# 12_Raspbbery_CM3.net
KiCad netlist of a schematic drawn in Altium Designer
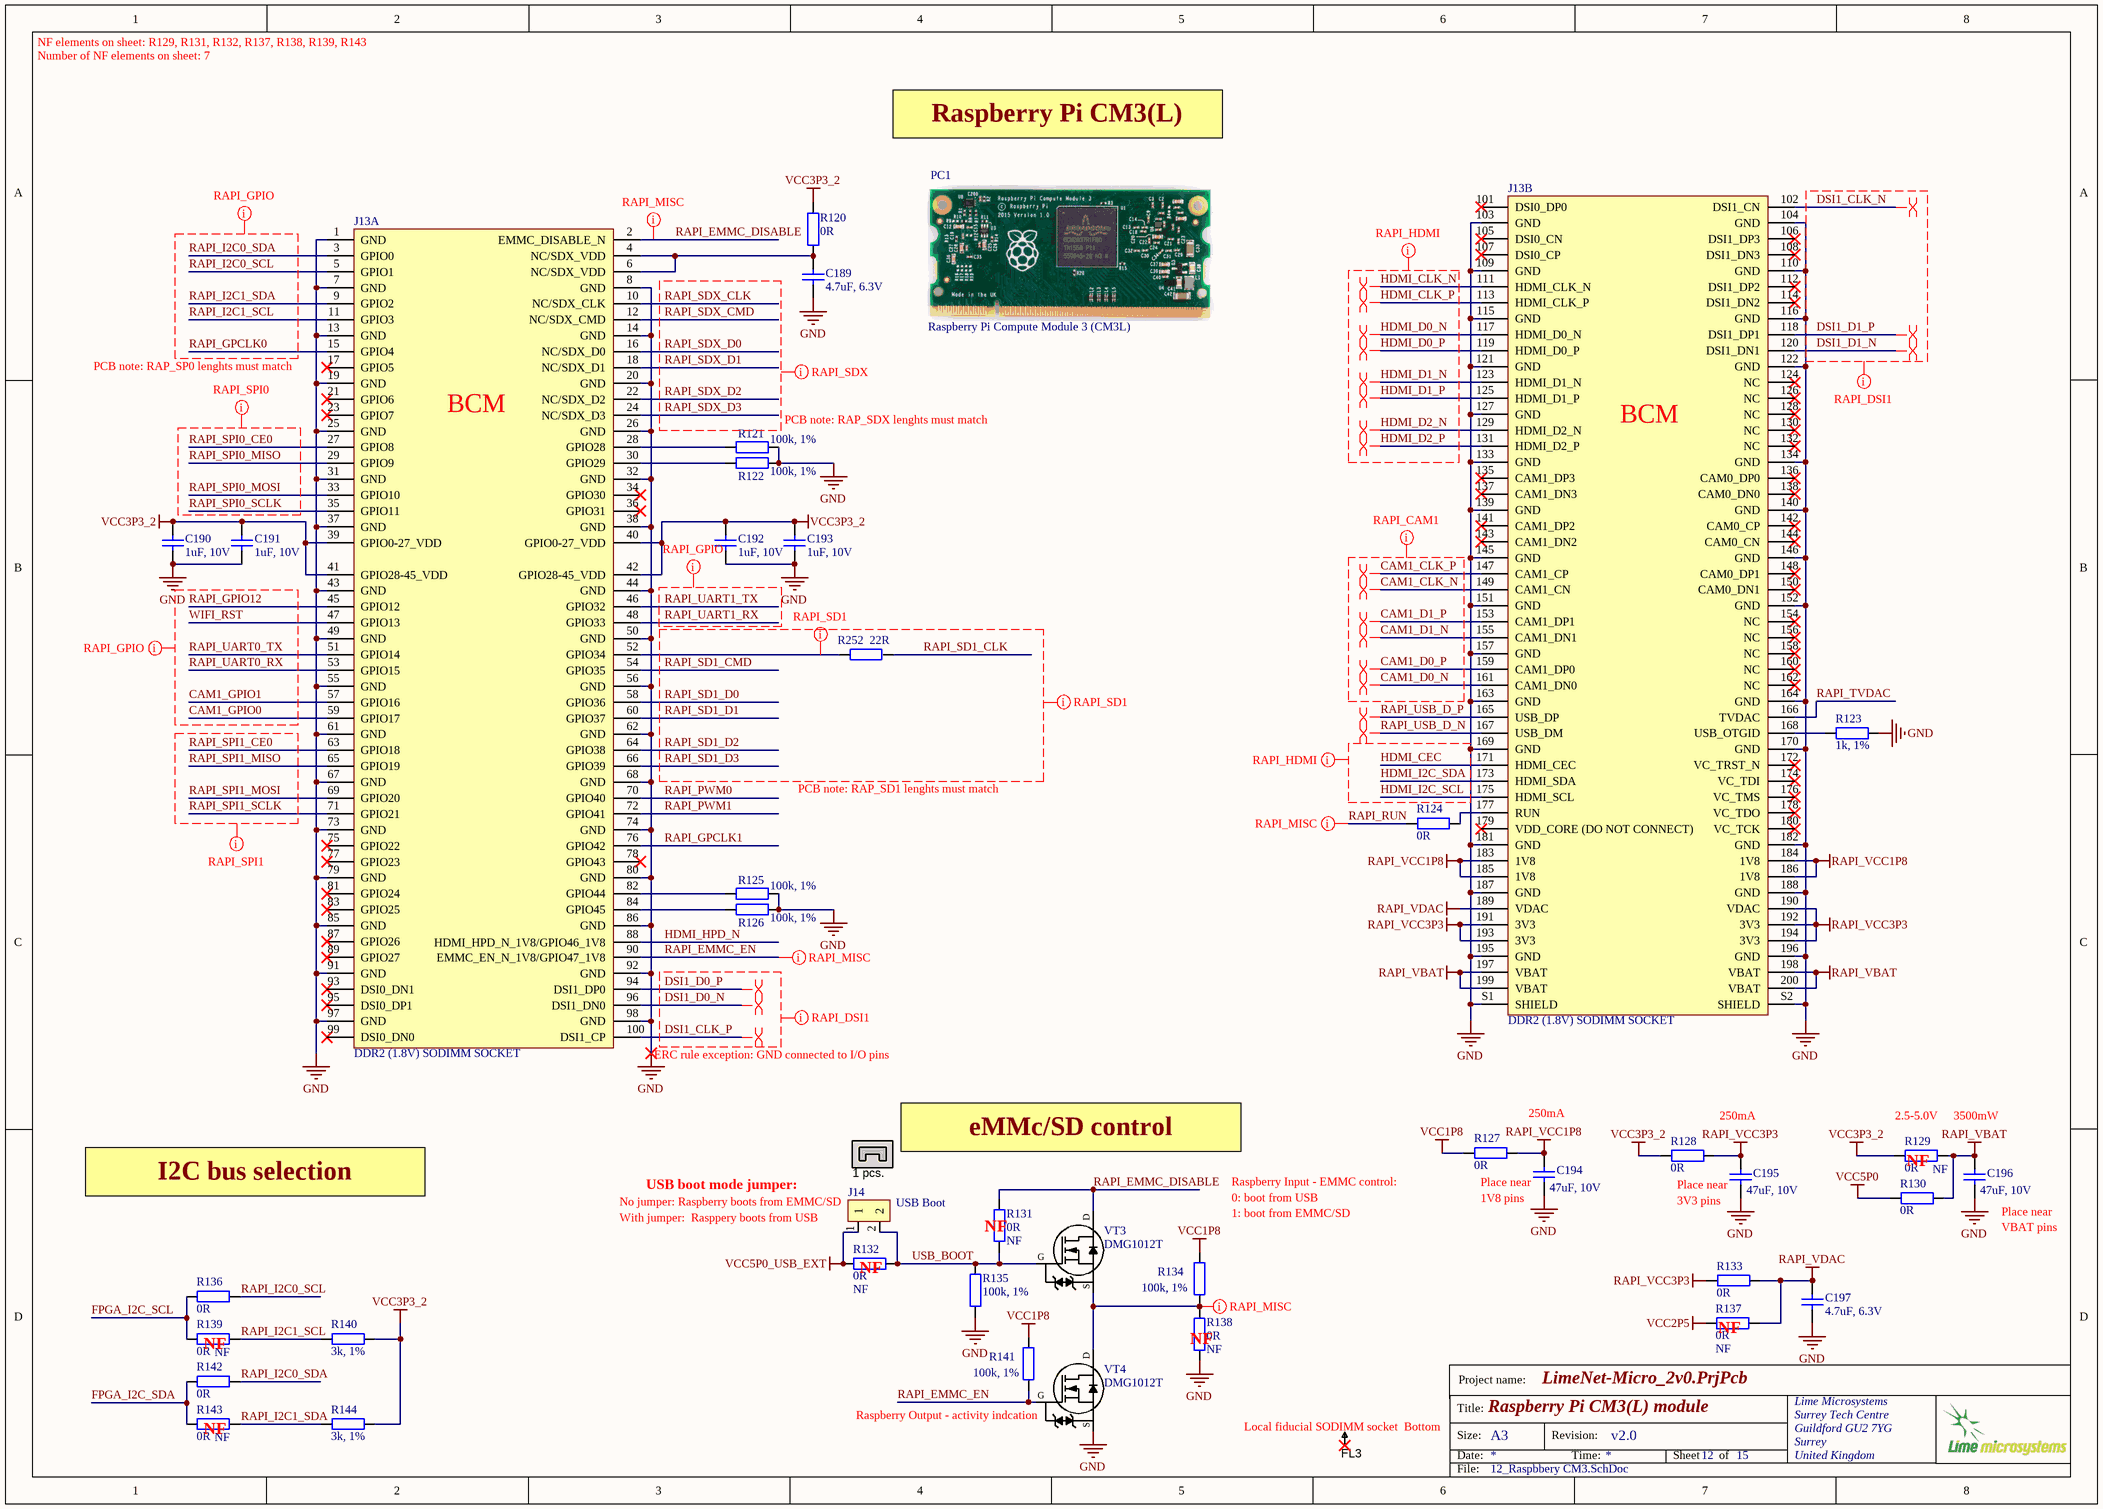
[diagram p0: 12_Raspbbery CM3.SchDoc]

(export (version "E")
  (design (tool "Eeschema 10.0.6"))
  (components
    (comp (ref "C189")
      (value "4.7uF, 6.3V")
      (footprint "CAP0402")
      (fields
        (field (name "MANUFACTURER") "Murata Electronics North America")
        (field (name "TOLERANCE") "±20%")
        (field (name "MANUFACTURER PART NUMBER") "GRM155R60J475ME87D")
      )
      (libsource (lib "LimeMicroAltiumLib_schLib") (part "Cap_0402"))
    )
    (comp (ref "C190")
      (value "1uF, 10V")
      (footprint "CAP0402")
      (description "CAP CER 1UF 10V X5R 0402")
      (fields
        (field (name "MANUFACTURER") "Yageo")
        (field (name "MANUFACTURER PART NUMBER") "CC0402MRX5R6BB105")
      )
      (libsource (lib "LimeMicroAltiumLib_schLib") (part "Cap_0402"))
    )
    (comp (ref "C191")
      (value "1uF, 10V")
      (footprint "CAP0402")
      (description "CAP CER 1UF 10V X5R 0402")
      (fields
        (field (name "MANUFACTURER") "Yageo")
        (field (name "MANUFACTURER PART NUMBER") "CC0402MRX5R6BB105")
      )
      (libsource (lib "LimeMicroAltiumLib_schLib") (part "Cap_0402"))
    )
    (comp (ref "C192")
      (value "1uF, 10V")
      (footprint "CAP0402")
      (description "CAP CER 1UF 10V X5R 0402")
      (fields
        (field (name "MANUFACTURER") "Yageo")
        (field (name "MANUFACTURER PART NUMBER") "CC0402MRX5R6BB105")
      )
      (libsource (lib "LimeMicroAltiumLib_schLib") (part "Cap_0402"))
    )
    (comp (ref "C193")
      (value "1uF, 10V")
      (footprint "CAP0402")
      (description "CAP CER 1UF 10V X5R 0402")
      (fields
        (field (name "MANUFACTURER") "Yageo")
        (field (name "MANUFACTURER PART NUMBER") "CC0402MRX5R6BB105")
      )
      (libsource (lib "LimeMicroAltiumLib_schLib") (part "Cap_0402"))
    )
    (comp (ref "C194")
      (value "47uF, 10V")
      (footprint "CAP1206")
      (fields (field (name "TOLERANCE") "±20%") (field (name "MANUFACTURER") "TDK Corporation"))
      (libsource (lib "LimeFPGAboard_schLib") (part "Cap_1206"))
    )
    (comp (ref "C195")
      (value "47uF, 10V")
      (footprint "CAP1206")
      (fields (field (name "TOLERANCE") "±20%") (field (name "MANUFACTURER") "TDK Corporation"))
      (libsource (lib "LimeFPGAboard_schLib") (part "Cap_1206"))
    )
    (comp (ref "C196")
      (value "47uF, 10V")
      (footprint "CAP1206")
      (fields (field (name "TOLERANCE") "±20%") (field (name "MANUFACTURER") "TDK Corporation"))
      (libsource (lib "LimeFPGAboard_schLib") (part "Cap_1206"))
    )
    (comp (ref "C197")
      (value "4.7uF, 6.3V")
      (footprint "CAP0402")
      (fields
        (field (name "MANUFACTURER") "Murata Electronics North America")
        (field (name "TOLERANCE") "±20%")
        (field (name "MANUFACTURER PART NUMBER") "GRM155R60J475ME87D")
      )
      (libsource (lib "LimeMicroAltiumLib_schLib") (part "Cap_0402"))
    )
    (comp (ref "FL3")
      (value "Fiducial")
      (footprint "Fiducial_local")
      (libsource (lib "VGTU_Altium_lib") (part "Fiducial"))
    )
    (comp (ref "J13")
      (value "DDR2 (1.8V) SODIMM SOCKET")
      (footprint "TE_1717254-1_DDR_SODIMM")
      (fields
        (field (name "MANUFACTURER") "TE Connectivity AMP Connectors")
        (field (name "MANUFACTURER PART NUMBER") "1717254-4")
      )
      (libsource (lib "LimeMicroAltiumLib_schLib_r01") (part "1717254-1"))
    )
    (comp (ref "J14")
      (value "USB Boot")
      (footprint "HDR_1x2")
      (fields (field (name "MANUFACTURER") "3M"))
      (libsource (lib "LimeFPGAboard_schLib") (part "Jumper"))
    )
    (comp (ref "JMP1")
      (value "1 pcs.")
      (description "Shorting Jumper, 2-position, 1.27mm pitch")
      (fields (field (name "MANUFACTURER") "Sullins"))
      (libsource (lib "LimeMicroAltiumLib_schLib") (part "JUMP_2P_CONN_HEADER"))
    )
    (comp (ref "PC1")
      (value "Raspberry Pi Compute Module 3 (CM3L)")
      (fields (field (name "MANUFACTURER") "RASPBERRY-PI"))
      (libsource (lib "LimeMicroAltiumLib_schLib_r01") (part "Raspberry_RPI-COMPUTE3"))
    )
    (comp (ref "R120")
      (value "0R")
      (footprint "RES0402")
      (fields (field (name "MANUFACTURER") "Yageo"))
      (libsource (lib "LimeFPGAboard_schLib") (part "Res_0402"))
    )
    (comp (ref "R121")
      (value "100k, 1%")
      (footprint "RES0402")
      (fields
        (field (name "MANUFACTURER") "Vishay Dale")
        (field (name "TOLERANCE") "±1%")
        (field (name "MANUFACTURER PART NUMBER") "CRCW0402100KFKEDC")
      )
      (libsource (lib "LimeMicroAltiumLib_schLib") (part "Res_0402"))
    )
    (comp (ref "R122")
      (value "100k, 1%")
      (footprint "RES0402")
      (fields
        (field (name "MANUFACTURER") "Vishay Dale")
        (field (name "TOLERANCE") "±1%")
        (field (name "MANUFACTURER PART NUMBER") "CRCW0402100KFKEDC")
      )
      (libsource (lib "LimeMicroAltiumLib_schLib") (part "Res_0402"))
    )
    (comp (ref "R123")
      (value "1k, 1%")
      (footprint "RES0402")
      (fields (field (name "MANUFACTURER") "Stackpole Electronics Inc") (field (name "TOLERANCE") "±1%"))
      (libsource (lib "LimeMicroAltiumLib_schLib") (part "Res_0402"))
    )
    (comp (ref "R124")
      (value "0R")
      (footprint "RES0402")
      (fields (field (name "MANUFACTURER") "Yageo"))
      (libsource (lib "LimeFPGAboard_schLib") (part "Res_0402"))
    )
    (comp (ref "R125")
      (value "100k, 1%")
      (footprint "RES0402")
      (fields
        (field (name "MANUFACTURER") "Vishay Dale")
        (field (name "TOLERANCE") "±1%")
        (field (name "MANUFACTURER PART NUMBER") "CRCW0402100KFKEDC")
      )
      (libsource (lib "LimeMicroAltiumLib_schLib") (part "Res_0402"))
    )
    (comp (ref "R126")
      (value "100k, 1%")
      (footprint "RES0402")
      (fields
        (field (name "MANUFACTURER") "Vishay Dale")
        (field (name "TOLERANCE") "±1%")
        (field (name "MANUFACTURER PART NUMBER") "CRCW0402100KFKEDC")
      )
      (libsource (lib "LimeMicroAltiumLib_schLib") (part "Res_0402"))
    )
    (comp (ref "R127")
      (value "0R")
      (footprint "RES0805")
      (fields (field (name "MANUFACTURER") "Vishay Dale") (field (name "TOLERANCE") "Jumper"))
      (libsource (lib "LimeMicroAltiumLib_schLib") (part "Res_0402"))
    )
    (comp (ref "R128")
      (value "0R")
      (footprint "RES0805")
      (fields (field (name "MANUFACTURER") "Vishay Dale") (field (name "TOLERANCE") "Jumper"))
      (libsource (lib "LimeMicroAltiumLib_schLib") (part "Res_0402"))
    )
    (comp (ref "R129")
      (value "0R")
      (footprint "RES0805")
      (fields
        (field (name "ASSEMBLY INFO") "NF")
        (field (name "MANUFACTURER") "Vishay Dale")
        (field (name "TOLERANCE") "Jumper")
      )
      (libsource (lib "LimeMicroAltiumLib_schLib") (part "Res_0402"))
    )
    (comp (ref "R130")
      (value "0R")
      (footprint "RES0805")
      (fields (field (name "MANUFACTURER") "Vishay Dale") (field (name "TOLERANCE") "Jumper"))
      (libsource (lib "LimeMicroAltiumLib_schLib") (part "Res_0402"))
    )
    (comp (ref "R131")
      (value "0R")
      (footprint "RES0402")
      (fields (field (name "MANUFACTURER") "Yageo") (field (name "ASSEMBLY INFO") "NF"))
      (libsource (lib "LimeFPGAboard_schLib") (part "Res_0402"))
    )
    (comp (ref "R132")
      (value "0R")
      (footprint "RES0402")
      (fields
        (field (name "ASSEMBLY INFO") "NF")
        (field (name "MANUFACTURER") "Yageo")
        (field (name "TOLERANCE") "Jumper")
      )
      (libsource (lib "LimeMicroAltiumLib_schLib") (part "Res_0402"))
    )
    (comp (ref "R133")
      (value "0R")
      (footprint "RES0402")
      (fields (field (name "MANUFACTURER") "Yageo"))
      (libsource (lib "LimeFPGAboard_schLib") (part "Res_0402"))
    )
    (comp (ref "R134")
      (value "100k, 1%")
      (footprint "RES0402")
      (fields
        (field (name "MANUFACTURER") "Vishay Dale")
        (field (name "TOLERANCE") "±1%")
        (field (name "MANUFACTURER PART NUMBER") "CRCW0402100KFKEDC")
      )
      (libsource (lib "LimeMicroAltiumLib_schLib") (part "Res_0402"))
    )
    (comp (ref "R135")
      (value "100k, 1%")
      (footprint "RES0402")
      (fields
        (field (name "MANUFACTURER") "Vishay Dale")
        (field (name "TOLERANCE") "±1%")
        (field (name "MANUFACTURER PART NUMBER") "CRCW0402100KFKEDC")
      )
      (libsource (lib "LimeMicroAltiumLib_schLib") (part "Res_0402"))
    )
    (comp (ref "R136")
      (value "0R")
      (footprint "RES0402")
      (fields (field (name "MANUFACTURER") "Yageo"))
      (libsource (lib "LimeFPGAboard_schLib") (part "Res_0402"))
    )
    (comp (ref "R137")
      (value "0R")
      (footprint "RES0402")
      (fields (field (name "MANUFACTURER") "Yageo") (field (name "ASSEMBLY INFO") "NF"))
      (libsource (lib "LimeFPGAboard_schLib") (part "Res_0402"))
    )
    (comp (ref "R138")
      (value "0R")
      (footprint "RES0402")
      (fields (field (name "MANUFACTURER") "Yageo") (field (name "ASSEMBLY INFO") "NF"))
      (libsource (lib "LimeFPGAboard_schLib") (part "Res_0402"))
    )
    (comp (ref "R139")
      (value "0R")
      (footprint "RES0402")
      (fields (field (name "MANUFACTURER") "Yageo") (field (name "ASSEMBLY INFO") "NF"))
      (libsource (lib "LimeFPGAboard_schLib") (part "Res_0402"))
    )
    (comp (ref "R140")
      (value "3k, 1%")
      (footprint "RES0402")
      (fields (field (name "TOLERANCE") "±1%") (field (name "MANUFACTURER") "Vishay Dale"))
      (libsource (lib "LimeMicroAltiumLib_schLib") (part "Res_0402"))
    )
    (comp (ref "R141")
      (value "100k, 1%")
      (footprint "RES0402")
      (fields
        (field (name "MANUFACTURER") "Vishay Dale")
        (field (name "TOLERANCE") "±1%")
        (field (name "MANUFACTURER PART NUMBER") "CRCW0402100KFKEDC")
      )
      (libsource (lib "LimeMicroAltiumLib_schLib") (part "Res_0402"))
    )
    (comp (ref "R142")
      (value "0R")
      (footprint "RES0402")
      (fields (field (name "MANUFACTURER") "Yageo"))
      (libsource (lib "LimeFPGAboard_schLib") (part "Res_0402"))
    )
    (comp (ref "R143")
      (value "0R")
      (footprint "RES0402")
      (fields (field (name "MANUFACTURER") "Yageo") (field (name "ASSEMBLY INFO") "NF"))
      (libsource (lib "LimeFPGAboard_schLib") (part "Res_0402"))
    )
    (comp (ref "R144")
      (value "3k, 1%")
      (footprint "RES0402")
      (fields (field (name "TOLERANCE") "±1%") (field (name "MANUFACTURER") "Vishay Dale"))
      (libsource (lib "LimeMicroAltiumLib_schLib") (part "Res_0402"))
    )
    (comp (ref "R252")
      (value "22R")
      (footprint "RES0402")
      (fields (field (name "TOLERANCE") "±1%") (field (name "MANUFACTURER") "Yageo"))
      (libsource (lib "LimeFPGAboard_schLib") (part "Res_0402"))
    )
    (comp (ref "VT3")
      (value "DMG1012T")
      (footprint "SOT523")
      (fields
        (field (name "MANUFACTURER") "Diodes Incorporated")
        (field (name "MANUFACTURER PART NUMBER") "DMG1012TQ-7")
      )
      (libsource (lib "LimeMicroAltiumLib_schLib_r01") (part "DMG1012T"))
    )
    (comp (ref "VT4")
      (value "DMG1012T")
      (footprint "SOT523")
      (fields
        (field (name "MANUFACTURER") "Diodes Incorporated")
        (field (name "MANUFACTURER PART NUMBER") "DMG1012TQ-7")
      )
      (libsource (lib "LimeMicroAltiumLib_schLib_r01") (part "DMG1012T"))
    )
  )
  (nets
    (net (code "1") (name "/CAM1_CLK_N") (class "Default")
      (node (ref "J13") (pin "149") (pinfunction "CAM1_CN_149") (pintype "passive"))
    )
    (net (code "2") (name "/CAM1_CLK_P") (class "Default")
      (node (ref "J13") (pin "147") (pinfunction "CAM1_CP_147") (pintype "passive"))
    )
    (net (code "3") (name "/CAM1_D0_N") (class "Default")
      (node (ref "J13") (pin "161") (pinfunction "CAM1_DN0_161") (pintype "passive"))
    )
    (net (code "4") (name "/CAM1_D0_P") (class "Default")
      (node (ref "J13") (pin "159") (pinfunction "CAM1_DP0_159") (pintype "passive"))
    )
    (net (code "5") (name "/CAM1_D1_N") (class "Default")
      (node (ref "J13") (pin "155") (pinfunction "CAM1_DN1_155") (pintype "passive"))
    )
    (net (code "6") (name "/CAM1_D1_P") (class "Default")
      (node (ref "J13") (pin "153") (pinfunction "CAM1_DP1_153") (pintype "passive"))
    )
    (net (code "7") (name "/CAM1_GPIO0") (class "Default")
      (node (ref "J13") (pin "59") (pinfunction "GPIO17_59") (pintype "passive"))
    )
    (net (code "8") (name "/CAM1_GPIO1") (class "Default")
      (node (ref "J13") (pin "57") (pinfunction "GPIO16_57") (pintype "passive"))
    )
    (net (code "9") (name "/DSI1_CLK_N") (class "Default")
      (node (ref "J13") (pin "102") (pinfunction "DSI1_CN_102") (pintype "passive"))
    )
    (net (code "10") (name "/DSI1_CLK_P") (class "Default")
      (node (ref "J13") (pin "100") (pinfunction "DSI1_CP_100") (pintype "passive"))
    )
    (net (code "11") (name "/DSI1_D0_N") (class "Default")
      (node (ref "J13") (pin "96") (pinfunction "DSI1_DN0_96") (pintype "passive"))
    )
    (net (code "12") (name "/DSI1_D0_P") (class "Default")
      (node (ref "J13") (pin "94") (pinfunction "DSI1_DP0_94") (pintype "passive"))
    )
    (net (code "13") (name "/DSI1_D1_N") (class "Default")
      (node (ref "J13") (pin "120") (pinfunction "DSI1_DN1_120") (pintype "passive"))
    )
    (net (code "14") (name "/DSI1_D1_P") (class "Default")
      (node (ref "J13") (pin "118") (pinfunction "DSI1_DP1_118") (pintype "passive"))
    )
    (net (code "15") (name "/FPGA_I2C_SCL") (class "Default")
      (node (ref "R136") (pin "1") (pinfunction "1_1") (pintype "passive"))
      (node (ref "R139") (pin "1") (pinfunction "1_1") (pintype "passive"))
    )
    (net (code "16") (name "/FPGA_I2C_SDA") (class "Default")
      (node (ref "R142") (pin "1") (pinfunction "1_1") (pintype "passive"))
      (node (ref "R143") (pin "1") (pinfunction "1_1") (pintype "passive"))
    )
    (net (code "17") (name "/HDMI_CEC") (class "Default")
      (node (ref "J13") (pin "171") (pinfunction "HDMI_CEC_171") (pintype "passive"))
    )
    (net (code "18") (name "/HDMI_CLK_N") (class "Default")
      (node (ref "J13") (pin "111") (pinfunction "HDMI_CLK_N_111") (pintype "passive"))
    )
    (net (code "19") (name "/HDMI_CLK_P") (class "Default")
      (node (ref "J13") (pin "113") (pinfunction "HDMI_CLK_P_113") (pintype "passive"))
    )
    (net (code "20") (name "/HDMI_D0_N") (class "Default")
      (node (ref "J13") (pin "117") (pinfunction "HDMI_D0_N_117") (pintype "passive"))
    )
    (net (code "21") (name "/HDMI_D0_P") (class "Default")
      (node (ref "J13") (pin "119") (pinfunction "HDMI_D0_P_119") (pintype "passive"))
    )
    (net (code "22") (name "/HDMI_D1_N") (class "Default")
      (node (ref "J13") (pin "123") (pinfunction "HDMI_D1_N_123") (pintype "passive"))
    )
    (net (code "23") (name "/HDMI_D1_P") (class "Default")
      (node (ref "J13") (pin "125") (pinfunction "HDMI_D1_P_125") (pintype "passive"))
    )
    (net (code "24") (name "/HDMI_D2_N") (class "Default")
      (node (ref "J13") (pin "129") (pinfunction "HDMI_D2_N_129") (pintype "passive"))
    )
    (net (code "25") (name "/HDMI_D2_P") (class "Default")
      (node (ref "J13") (pin "131") (pinfunction "HDMI_D2_P_131") (pintype "passive"))
    )
    (net (code "26") (name "/HDMI_HPD_N") (class "Default")
      (node (ref "J13") (pin "88") (pinfunction "HDMI_HPD_N_1V8/GPIO46_1V8_88") (pintype "passive"))
    )
    (net (code "27") (name "/HDMI_I2C_SCL") (class "Default")
      (node (ref "J13") (pin "175") (pinfunction "HDMI_SCL_175") (pintype "passive"))
    )
    (net (code "28") (name "/HDMI_I2C_SDA") (class "Default")
      (node (ref "J13") (pin "173") (pinfunction "HDMI_SDA_173") (pintype "passive"))
    )
    (net (code "29") (name "/RAPI_EMMC_DISABLE") (class "Default")
      (node (ref "J13") (pin "2") (pinfunction "EMMC_DISABLE_N_2") (pintype "passive"))
      (node (ref "R131") (pin "1") (pinfunction "1_1") (pintype "passive"))
      (node (ref "VT3") (pin "D") (pinfunction "D_D") (pintype "passive"))
    )
    (net (code "30") (name "/RAPI_EMMC_EN") (class "Default")
      (node (ref "J13") (pin "90") (pinfunction "EMMC_EN_N_1V8/GPIO47_1V8_90") (pintype "passive"))
      (node (ref "R141") (pin "2") (pinfunction "2_2") (pintype "passive"))
      (node (ref "VT4") (pin "G") (pinfunction "G_G") (pintype "passive"))
    )
    (net (code "31") (name "/RAPI_GPCLK0") (class "Default")
      (node (ref "J13") (pin "15") (pinfunction "GPIO4_15") (pintype "passive"))
    )
    (net (code "32") (name "/RAPI_GPCLK1") (class "Default")
      (node (ref "J13") (pin "76") (pinfunction "GPIO42_76") (pintype "passive"))
    )
    (net (code "33") (name "/RAPI_GPIO12") (class "Default")
      (node (ref "J13") (pin "45") (pinfunction "GPIO12_45") (pintype "passive"))
    )
    (net (code "34") (name "/RAPI_I2C0_SCL") (class "Default")
      (node (ref "J13") (pin "5") (pinfunction "GPIO1_5") (pintype "passive"))
      (node (ref "R136") (pin "2") (pinfunction "2_2") (pintype "passive"))
    )
    (net (code "35") (name "/RAPI_I2C0_SDA") (class "Default")
      (node (ref "J13") (pin "3") (pinfunction "GPIO0_3") (pintype "passive"))
      (node (ref "R142") (pin "2") (pinfunction "2_2") (pintype "passive"))
    )
    (net (code "36") (name "/RAPI_I2C1_SCL") (class "Default")
      (node (ref "J13") (pin "11") (pinfunction "GPIO3_11") (pintype "passive"))
      (node (ref "R139") (pin "2") (pinfunction "2_2") (pintype "passive"))
      (node (ref "R140") (pin "2") (pinfunction "2_2") (pintype "passive"))
    )
    (net (code "37") (name "/RAPI_I2C1_SDA") (class "Default")
      (node (ref "J13") (pin "9") (pinfunction "GPIO2_9") (pintype "passive"))
      (node (ref "R143") (pin "2") (pinfunction "2_2") (pintype "passive"))
      (node (ref "R144") (pin "2") (pinfunction "2_2") (pintype "passive"))
    )
    (net (code "38") (name "/RAPI_PWM0") (class "Default")
      (node (ref "J13") (pin "70") (pinfunction "GPIO40_70") (pintype "passive"))
    )
    (net (code "39") (name "/RAPI_PWM1") (class "Default")
      (node (ref "J13") (pin "72") (pinfunction "GPIO41_72") (pintype "passive"))
    )
    (net (code "40") (name "/RAPI_RUN") (class "Default")
      (node (ref "R124") (pin "2") (pinfunction "2_2") (pintype "passive"))
    )
    (net (code "41") (name "/RAPI_SD1_CLK") (class "Default")
      (node (ref "R252") (pin "2") (pinfunction "2_2") (pintype "passive"))
    )
    (net (code "42") (name "/RAPI_SD1_CMD") (class "Default")
      (node (ref "J13") (pin "54") (pinfunction "GPIO35_54") (pintype "passive"))
    )
    (net (code "43") (name "/RAPI_SD1_D0") (class "Default")
      (node (ref "J13") (pin "58") (pinfunction "GPIO36_58") (pintype "passive"))
    )
    (net (code "44") (name "/RAPI_SD1_D1") (class "Default")
      (node (ref "J13") (pin "60") (pinfunction "GPIO37_60") (pintype "passive"))
    )
    (net (code "45") (name "/RAPI_SD1_D2") (class "Default")
      (node (ref "J13") (pin "64") (pinfunction "GPIO38_64") (pintype "passive"))
    )
    (net (code "46") (name "/RAPI_SD1_D3") (class "Default")
      (node (ref "J13") (pin "66") (pinfunction "GPIO39_66") (pintype "passive"))
    )
    (net (code "47") (name "/RAPI_SDX_CLK") (class "Default")
      (node (ref "J13") (pin "10") (pinfunction "NC/SDX_CLK_10") (pintype "passive"))
    )
    (net (code "48") (name "/RAPI_SDX_CMD") (class "Default")
      (node (ref "J13") (pin "12") (pinfunction "NC/SDX_CMD_12") (pintype "passive"))
    )
    (net (code "49") (name "/RAPI_SDX_D0") (class "Default")
      (node (ref "J13") (pin "16") (pinfunction "NC/SDX_D0_16") (pintype "passive"))
    )
    (net (code "50") (name "/RAPI_SDX_D1") (class "Default")
      (node (ref "J13") (pin "18") (pinfunction "NC/SDX_D1_18") (pintype "passive"))
    )
    (net (code "51") (name "/RAPI_SDX_D2") (class "Default")
      (node (ref "J13") (pin "22") (pinfunction "NC/SDX_D2_22") (pintype "passive"))
    )
    (net (code "52") (name "/RAPI_SDX_D3") (class "Default")
      (node (ref "J13") (pin "24") (pinfunction "NC/SDX_D3_24") (pintype "passive"))
    )
    (net (code "53") (name "/RAPI_SPI0_CE0") (class "Default")
      (node (ref "J13") (pin "27") (pinfunction "GPIO8_27") (pintype "passive"))
    )
    (net (code "54") (name "/RAPI_SPI0_MISO") (class "Default")
      (node (ref "J13") (pin "29") (pinfunction "GPIO9_29") (pintype "passive"))
    )
    (net (code "55") (name "/RAPI_SPI0_MOSI") (class "Default")
      (node (ref "J13") (pin "33") (pinfunction "GPIO10_33") (pintype "passive"))
    )
    (net (code "56") (name "/RAPI_SPI0_SCLK") (class "Default")
      (node (ref "J13") (pin "35") (pinfunction "GPIO11_35") (pintype "passive"))
    )
    (net (code "57") (name "/RAPI_SPI1_CE0") (class "Default")
      (node (ref "J13") (pin "63") (pinfunction "GPIO18_63") (pintype "passive"))
    )
    (net (code "58") (name "/RAPI_SPI1_MISO") (class "Default")
      (node (ref "J13") (pin "65") (pinfunction "GPIO19_65") (pintype "passive"))
    )
    (net (code "59") (name "/RAPI_SPI1_MOSI") (class "Default")
      (node (ref "J13") (pin "69") (pinfunction "GPIO20_69") (pintype "passive"))
    )
    (net (code "60") (name "/RAPI_SPI1_SCLK") (class "Default")
      (node (ref "J13") (pin "71") (pinfunction "GPIO21_71") (pintype "passive"))
    )
    (net (code "61") (name "/RAPI_TVDAC") (class "Default")
      (node (ref "J13") (pin "166") (pinfunction "TVDAC_166") (pintype "passive"))
    )
    (net (code "62") (name "/RAPI_UART0_RX") (class "Default")
      (node (ref "J13") (pin "53") (pinfunction "GPIO15_53") (pintype "passive"))
    )
    (net (code "63") (name "/RAPI_UART0_TX") (class "Default")
      (node (ref "J13") (pin "51") (pinfunction "GPIO14_51") (pintype "passive"))
    )
    (net (code "64") (name "/RAPI_UART1_RX") (class "Default")
      (node (ref "J13") (pin "48") (pinfunction "GPIO33_48") (pintype "passive"))
    )
    (net (code "65") (name "/RAPI_UART1_TX") (class "Default")
      (node (ref "J13") (pin "46") (pinfunction "GPIO32_46") (pintype "passive"))
    )
    (net (code "66") (name "/RAPI_USB_D_N") (class "Default")
      (node (ref "J13") (pin "167") (pinfunction "USB_DM_167") (pintype "passive"))
    )
    (net (code "67") (name "/RAPI_USB_D_P") (class "Default")
      (node (ref "J13") (pin "165") (pinfunction "USB_DP_165") (pintype "passive"))
    )
    (net (code "68") (name "/USB_BOOT") (class "Default")
      (node (ref "J14") (pin "2") (pinfunction "2_2") (pintype "passive"))
      (node (ref "R131") (pin "2") (pinfunction "2_2") (pintype "passive"))
      (node (ref "R132") (pin "2") (pinfunction "2_2") (pintype "passive"))
      (node (ref "R135") (pin "1") (pinfunction "1_1") (pintype "passive"))
      (node (ref "VT3") (pin "G") (pinfunction "G_G") (pintype "passive"))
    )
    (net (code "69") (name "/WIFI_RST") (class "Default")
      (node (ref "J13") (pin "47") (pinfunction "GPIO13_47") (pintype "passive"))
    )
    (net (code "70") (name "GND") (class "Default")
      (node (ref "C189") (pin "2") (pinfunction "2_2") (pintype "passive"))
      (node (ref "C190") (pin "1") (pinfunction "1_1") (pintype "passive"))
      (node (ref "C191") (pin "1") (pinfunction "1_1") (pintype "passive"))
      (node (ref "C192") (pin "1") (pinfunction "1_1") (pintype "passive"))
      (node (ref "C193") (pin "1") (pinfunction "1_1") (pintype "passive"))
      (node (ref "C194") (pin "1") (pinfunction "1_1") (pintype "passive"))
      (node (ref "C195") (pin "1") (pinfunction "1_1") (pintype "passive"))
      (node (ref "C196") (pin "1") (pinfunction "1_1") (pintype "passive"))
      (node (ref "C197") (pin "1") (pinfunction "1_1") (pintype "passive"))
      (node (ref "J13") (pin "1") (pinfunction "GND_1") (pintype "passive"))
      (node (ref "J13") (pin "103") (pinfunction "GND_103") (pintype "passive"))
      (node (ref "J13") (pin "104") (pinfunction "GND_104") (pintype "passive"))
      (node (ref "J13") (pin "109") (pinfunction "GND_109") (pintype "passive"))
      (node (ref "J13") (pin "110") (pinfunction "GND_110") (pintype "passive"))
      (node (ref "J13") (pin "115") (pinfunction "GND_115") (pintype "passive"))
      (node (ref "J13") (pin "116") (pinfunction "GND_116") (pintype "passive"))
      (node (ref "J13") (pin "121") (pinfunction "GND_121") (pintype "passive"))
      (node (ref "J13") (pin "122") (pinfunction "GND_122") (pintype "passive"))
      (node (ref "J13") (pin "127") (pinfunction "GND_127") (pintype "passive"))
      (node (ref "J13") (pin "13") (pinfunction "GND_13") (pintype "passive"))
      (node (ref "J13") (pin "133") (pinfunction "GND_133") (pintype "passive"))
      (node (ref "J13") (pin "134") (pinfunction "GND_134") (pintype "passive"))
      (node (ref "J13") (pin "139") (pinfunction "GND_139") (pintype "passive"))
      (node (ref "J13") (pin "14") (pinfunction "GND_14") (pintype "passive"))
      (node (ref "J13") (pin "140") (pinfunction "GND_140") (pintype "passive"))
      (node (ref "J13") (pin "145") (pinfunction "GND_145") (pintype "passive"))
      (node (ref "J13") (pin "146") (pinfunction "GND_146") (pintype "passive"))
      (node (ref "J13") (pin "151") (pinfunction "GND_151") (pintype "passive"))
      (node (ref "J13") (pin "152") (pinfunction "GND_152") (pintype "passive"))
      (node (ref "J13") (pin "157") (pinfunction "GND_157") (pintype "passive"))
      (node (ref "J13") (pin "163") (pinfunction "GND_163") (pintype "passive"))
      (node (ref "J13") (pin "164") (pinfunction "GND_164") (pintype "passive"))
      (node (ref "J13") (pin "169") (pinfunction "GND_169") (pintype "passive"))
      (node (ref "J13") (pin "170") (pinfunction "GND_170") (pintype "passive"))
      (node (ref "J13") (pin "181") (pinfunction "GND_181") (pintype "passive"))
      (node (ref "J13") (pin "182") (pinfunction "GND_182") (pintype "passive"))
      (node (ref "J13") (pin "187") (pinfunction "GND_187") (pintype "passive"))
      (node (ref "J13") (pin "188") (pinfunction "GND_188") (pintype "passive"))
      (node (ref "J13") (pin "19") (pinfunction "GND_19") (pintype "passive"))
      (node (ref "J13") (pin "195") (pinfunction "GND_195") (pintype "passive"))
      (node (ref "J13") (pin "196") (pinfunction "GND_196") (pintype "passive"))
      (node (ref "J13") (pin "20") (pinfunction "GND_20") (pintype "passive"))
      (node (ref "J13") (pin "25") (pinfunction "GND_25") (pintype "passive"))
      (node (ref "J13") (pin "26") (pinfunction "GND_26") (pintype "passive"))
      (node (ref "J13") (pin "31") (pinfunction "GND_31") (pintype "passive"))
      (node (ref "J13") (pin "32") (pinfunction "GND_32") (pintype "passive"))
      (node (ref "J13") (pin "37") (pinfunction "GND_37") (pintype "passive"))
      (node (ref "J13") (pin "38") (pinfunction "GND_38") (pintype "passive"))
      (node (ref "J13") (pin "43") (pinfunction "GND_43") (pintype "passive"))
      (node (ref "J13") (pin "44") (pinfunction "GND_44") (pintype "passive"))
      (node (ref "J13") (pin "49") (pinfunction "GND_49") (pintype "passive"))
      (node (ref "J13") (pin "50") (pinfunction "GND_50") (pintype "passive"))
      (node (ref "J13") (pin "55") (pinfunction "GND_55") (pintype "passive"))
      (node (ref "J13") (pin "56") (pinfunction "GND_56") (pintype "passive"))
      (node (ref "J13") (pin "61") (pinfunction "GND_61") (pintype "passive"))
      (node (ref "J13") (pin "62") (pinfunction "GND_62") (pintype "passive"))
      (node (ref "J13") (pin "67") (pinfunction "GND_67") (pintype "passive"))
      (node (ref "J13") (pin "68") (pinfunction "GND_68") (pintype "passive"))
      (node (ref "J13") (pin "7") (pinfunction "GND_7") (pintype "passive"))
      (node (ref "J13") (pin "73") (pinfunction "GND_73") (pintype "passive"))
      (node (ref "J13") (pin "74") (pinfunction "GND_74") (pintype "passive"))
      (node (ref "J13") (pin "79") (pinfunction "GND_79") (pintype "passive"))
      (node (ref "J13") (pin "8") (pinfunction "GND_8") (pintype "passive"))
      (node (ref "J13") (pin "80") (pinfunction "GND_80") (pintype "passive"))
      (node (ref "J13") (pin "85") (pinfunction "GND_85") (pintype "passive"))
      (node (ref "J13") (pin "86") (pinfunction "GND_86") (pintype "passive"))
      (node (ref "J13") (pin "91") (pinfunction "GND_91") (pintype "passive"))
      (node (ref "J13") (pin "92") (pinfunction "GND_92") (pintype "passive"))
      (node (ref "J13") (pin "97") (pinfunction "GND_97") (pintype "passive"))
      (node (ref "J13") (pin "98") (pinfunction "GND_98") (pintype "passive"))
      (node (ref "J13") (pin "S1") (pinfunction "SHIELD_S1") (pintype "passive"))
      (node (ref "J13") (pin "S2") (pinfunction "SHIELD_S2") (pintype "passive"))
      (node (ref "R121") (pin "1") (pinfunction "1_1") (pintype "passive"))
      (node (ref "R122") (pin "1") (pinfunction "1_1") (pintype "passive"))
      (node (ref "R123") (pin "1") (pinfunction "1_1") (pintype "passive"))
      (node (ref "R125") (pin "1") (pinfunction "1_1") (pintype "passive"))
      (node (ref "R126") (pin "1") (pinfunction "1_1") (pintype "passive"))
      (node (ref "R135") (pin "2") (pinfunction "2_2") (pintype "passive"))
      (node (ref "R138") (pin "1") (pinfunction "1_1") (pintype "passive"))
      (node (ref "VT4") (pin "S") (pinfunction "S_S") (pintype "passive"))
    )
    (net (code "71") (name "Net-(C189-Pad1)") (class "Default")
      (node (ref "C189") (pin "1") (pinfunction "1_1") (pintype "passive"))
      (node (ref "J13") (pin "4") (pinfunction "NC/SDX_VDD_4") (pintype "passive"))
      (node (ref "J13") (pin "6") (pinfunction "NC/SDX_VDD_6") (pintype "passive"))
      (node (ref "R120") (pin "1") (pinfunction "1_1") (pintype "passive"))
    )
    (net (code "72") (name "Net-(J13A-GPIO28)") (class "Default")
      (node (ref "J13") (pin "28") (pinfunction "GPIO28_28") (pintype "passive"))
      (node (ref "R121") (pin "2") (pinfunction "2_2") (pintype "passive"))
    )
    (net (code "73") (name "Net-(J13A-GPIO29)") (class "Default")
      (node (ref "J13") (pin "30") (pinfunction "GPIO29_30") (pintype "passive"))
      (node (ref "R122") (pin "2") (pinfunction "2_2") (pintype "passive"))
    )
    (net (code "74") (name "Net-(J13A-GPIO34)") (class "Default")
      (node (ref "J13") (pin "52") (pinfunction "GPIO34_52") (pintype "passive"))
      (node (ref "R252") (pin "1") (pinfunction "1_1") (pintype "passive"))
    )
    (net (code "75") (name "Net-(J13A-GPIO44)") (class "Default")
      (node (ref "J13") (pin "82") (pinfunction "GPIO44_82") (pintype "passive"))
      (node (ref "R125") (pin "2") (pinfunction "2_2") (pintype "passive"))
    )
    (net (code "76") (name "Net-(J13A-GPIO45)") (class "Default")
      (node (ref "J13") (pin "84") (pinfunction "GPIO45_84") (pintype "passive"))
      (node (ref "R126") (pin "2") (pinfunction "2_2") (pintype "passive"))
    )
    (net (code "77") (name "Net-(J13B-RUN)") (class "Default")
      (node (ref "J13") (pin "177") (pinfunction "RUN_177") (pintype "passive"))
      (node (ref "R124") (pin "1") (pinfunction "1_1") (pintype "passive"))
    )
    (net (code "78") (name "Net-(J13B-USB_OTGID)") (class "Default")
      (node (ref "J13") (pin "168") (pinfunction "USB_OTGID_168") (pintype "passive"))
      (node (ref "R123") (pin "2") (pinfunction "2_2") (pintype "passive"))
    )
    (net (code "79") (name "Net-(R134-Pad2)") (class "Default")
      (node (ref "R134") (pin "2") (pinfunction "2_2") (pintype "passive"))
      (node (ref "R138") (pin "2") (pinfunction "2_2") (pintype "passive"))
      (node (ref "VT3") (pin "S") (pinfunction "S_S") (pintype "passive"))
      (node (ref "VT4") (pin "D") (pinfunction "D_D") (pintype "passive"))
    )
    (net (code "80") (name "RAPI_VBAT") (class "Default")
      (node (ref "C196") (pin "2") (pinfunction "2_2") (pintype "passive"))
      (node (ref "J13") (pin "197") (pinfunction "VBAT_197") (pintype "passive"))
      (node (ref "J13") (pin "198") (pinfunction "VBAT_198") (pintype "passive"))
      (node (ref "J13") (pin "199") (pinfunction "VBAT_199") (pintype "passive"))
      (node (ref "J13") (pin "200") (pinfunction "VBAT_200") (pintype "passive"))
      (node (ref "R129") (pin "1") (pinfunction "1_1") (pintype "passive"))
      (node (ref "R130") (pin "1") (pinfunction "1_1") (pintype "passive"))
    )
    (net (code "81") (name "RAPI_VCC1P8") (class "Default")
      (node (ref "C194") (pin "2") (pinfunction "2_2") (pintype "passive"))
      (node (ref "J13") (pin "183") (pinfunction "1V8_183") (pintype "passive"))
      (node (ref "J13") (pin "184") (pinfunction "1V8_184") (pintype "passive"))
      (node (ref "J13") (pin "185") (pinfunction "1V8_185") (pintype "passive"))
      (node (ref "J13") (pin "186") (pinfunction "1V8_186") (pintype "passive"))
      (node (ref "R127") (pin "1") (pinfunction "1_1") (pintype "passive"))
    )
    (net (code "82") (name "RAPI_VCC3P3") (class "Default")
      (node (ref "C195") (pin "2") (pinfunction "2_2") (pintype "passive"))
      (node (ref "J13") (pin "190") (pinfunction "VDAC_190") (pintype "passive"))
      (node (ref "J13") (pin "191") (pinfunction "3V3_191") (pintype "passive"))
      (node (ref "J13") (pin "192") (pinfunction "3V3_192") (pintype "passive"))
      (node (ref "J13") (pin "193") (pinfunction "3V3_193") (pintype "passive"))
      (node (ref "J13") (pin "194") (pinfunction "3V3_194") (pintype "passive"))
      (node (ref "R128") (pin "1") (pinfunction "1_1") (pintype "passive"))
      (node (ref "R133") (pin "2") (pinfunction "2_2") (pintype "passive"))
    )
    (net (code "83") (name "RAPI_VDAC") (class "Default")
      (node (ref "C197") (pin "2") (pinfunction "2_2") (pintype "passive"))
      (node (ref "J13") (pin "189") (pinfunction "VDAC_189") (pintype "passive"))
      (node (ref "R133") (pin "1") (pinfunction "1_1") (pintype "passive"))
      (node (ref "R137") (pin "2") (pinfunction "2_2") (pintype "passive"))
    )
    (net (code "84") (name "VCC1P8") (class "Default")
      (node (ref "R127") (pin "2") (pinfunction "2_2") (pintype "passive"))
      (node (ref "R134") (pin "1") (pinfunction "1_1") (pintype "passive"))
      (node (ref "R141") (pin "1") (pinfunction "1_1") (pintype "passive"))
    )
    (net (code "85") (name "VCC2P5") (class "Default")
      (node (ref "R137") (pin "1") (pinfunction "1_1") (pintype "passive"))
    )
    (net (code "86") (name "VCC3P3_2") (class "Default")
      (node (ref "C190") (pin "2") (pinfunction "2_2") (pintype "passive"))
      (node (ref "C191") (pin "2") (pinfunction "2_2") (pintype "passive"))
      (node (ref "C192") (pin "2") (pinfunction "2_2") (pintype "passive"))
      (node (ref "C193") (pin "2") (pinfunction "2_2") (pintype "passive"))
      (node (ref "J13") (pin "39") (pinfunction "GPIO0-27_VDD_39") (pintype "passive"))
      (node (ref "J13") (pin "40") (pinfunction "GPIO0-27_VDD_40") (pintype "passive"))
      (node (ref "J13") (pin "41") (pinfunction "GPIO28-45_VDD_41") (pintype "passive"))
      (node (ref "J13") (pin "42") (pinfunction "GPIO28-45_VDD_42") (pintype "passive"))
      (node (ref "R120") (pin "2") (pinfunction "2_2") (pintype "passive"))
      (node (ref "R128") (pin "2") (pinfunction "2_2") (pintype "passive"))
      (node (ref "R129") (pin "2") (pinfunction "2_2") (pintype "passive"))
      (node (ref "R140") (pin "1") (pinfunction "1_1") (pintype "passive"))
      (node (ref "R144") (pin "1") (pinfunction "1_1") (pintype "passive"))
    )
    (net (code "87") (name "VCC5P0") (class "Default")
      (node (ref "R130") (pin "2") (pinfunction "2_2") (pintype "passive"))
    )
    (net (code "88") (name "VCC5P0_USB_EXT") (class "Default")
      (node (ref "J14") (pin "1") (pinfunction "1_1") (pintype "passive"))
      (node (ref "R132") (pin "1") (pinfunction "1_1") (pintype "passive"))
    )
    (net (code "89") (name "unconnected-(FL3-Pad1)") (class "Default")
      (node (ref "FL3") (pin "1") (pintype "passive+no_connect"))
    )
    (net (code "90") (name "unconnected-(J13A-DSI0_DN0-Pad99)") (class "Default")
      (node (ref "J13") (pin "99") (pinfunction "DSI0_DN0_99") (pintype "passive+no_connect"))
    )
    (net (code "91") (name "unconnected-(J13A-DSI0_DN1-Pad93)") (class "Default")
      (node (ref "J13") (pin "93") (pinfunction "DSI0_DN1_93") (pintype "passive+no_connect"))
    )
    (net (code "92") (name "unconnected-(J13A-DSI0_DP1-Pad95)") (class "Default")
      (node (ref "J13") (pin "95") (pinfunction "DSI0_DP1_95") (pintype "passive+no_connect"))
    )
    (net (code "93") (name "unconnected-(J13A-GPIO5-Pad17)") (class "Default")
      (node (ref "J13") (pin "17") (pinfunction "GPIO5_17") (pintype "passive+no_connect"))
    )
    (net (code "94") (name "unconnected-(J13A-GPIO6-Pad21)") (class "Default")
      (node (ref "J13") (pin "21") (pinfunction "GPIO6_21") (pintype "passive+no_connect"))
    )
    (net (code "95") (name "unconnected-(J13A-GPIO7-Pad23)") (class "Default")
      (node (ref "J13") (pin "23") (pinfunction "GPIO7_23") (pintype "passive+no_connect"))
    )
    (net (code "96") (name "unconnected-(J13A-GPIO22-Pad75)") (class "Default")
      (node (ref "J13") (pin "75") (pinfunction "GPIO22_75") (pintype "passive+no_connect"))
    )
    (net (code "97") (name "unconnected-(J13A-GPIO23-Pad77)") (class "Default")
      (node (ref "J13") (pin "77") (pinfunction "GPIO23_77") (pintype "passive+no_connect"))
    )
    (net (code "98") (name "unconnected-(J13A-GPIO24-Pad81)") (class "Default")
      (node (ref "J13") (pin "81") (pinfunction "GPIO24_81") (pintype "passive+no_connect"))
    )
    (net (code "99") (name "unconnected-(J13A-GPIO25-Pad83)") (class "Default")
      (node (ref "J13") (pin "83") (pinfunction "GPIO25_83") (pintype "passive+no_connect"))
    )
    (net (code "100") (name "unconnected-(J13A-GPIO26-Pad87)") (class "Default")
      (node (ref "J13") (pin "87") (pinfunction "GPIO26_87") (pintype "passive+no_connect"))
    )
    (net (code "101") (name "unconnected-(J13A-GPIO27-Pad89)") (class "Default")
      (node (ref "J13") (pin "89") (pinfunction "GPIO27_89") (pintype "passive+no_connect"))
    )
    (net (code "102") (name "unconnected-(J13A-GPIO30-Pad34)") (class "Default")
      (node (ref "J13") (pin "34") (pinfunction "GPIO30_34") (pintype "passive+no_connect"))
    )
    (net (code "103") (name "unconnected-(J13A-GPIO31-Pad36)") (class "Default")
      (node (ref "J13") (pin "36") (pinfunction "GPIO31_36") (pintype "passive+no_connect"))
    )
    (net (code "104") (name "unconnected-(J13A-GPIO43-Pad78)") (class "Default")
      (node (ref "J13") (pin "78") (pinfunction "GPIO43_78") (pintype "passive+no_connect"))
    )
    (net (code "105") (name "unconnected-(J13B-CAM0_CN-Pad144)") (class "Default")
      (node (ref "J13") (pin "144") (pinfunction "CAM0_CN_144") (pintype "passive+no_connect"))
    )
    (net (code "106") (name "unconnected-(J13B-CAM0_CP-Pad142)") (class "Default")
      (node (ref "J13") (pin "142") (pinfunction "CAM0_CP_142") (pintype "passive+no_connect"))
    )
    (net (code "107") (name "unconnected-(J13B-CAM0_DN0-Pad138)") (class "Default")
      (node (ref "J13") (pin "138") (pinfunction "CAM0_DN0_138") (pintype "passive+no_connect"))
    )
    (net (code "108") (name "unconnected-(J13B-CAM0_DN1-Pad150)") (class "Default")
      (node (ref "J13") (pin "150") (pinfunction "CAM0_DN1_150") (pintype "passive+no_connect"))
    )
    (net (code "109") (name "unconnected-(J13B-CAM0_DP0-Pad136)") (class "Default")
      (node (ref "J13") (pin "136") (pinfunction "CAM0_DP0_136") (pintype "passive+no_connect"))
    )
    (net (code "110") (name "unconnected-(J13B-CAM0_DP1-Pad148)") (class "Default")
      (node (ref "J13") (pin "148") (pinfunction "CAM0_DP1_148") (pintype "passive+no_connect"))
    )
    (net (code "111") (name "unconnected-(J13B-CAM1_DN2-Pad143)") (class "Default")
      (node (ref "J13") (pin "143") (pinfunction "CAM1_DN2_143") (pintype "passive+no_connect"))
    )
    (net (code "112") (name "unconnected-(J13B-CAM1_DN3-Pad137)") (class "Default")
      (node (ref "J13") (pin "137") (pinfunction "CAM1_DN3_137") (pintype "passive+no_connect"))
    )
    (net (code "113") (name "unconnected-(J13B-CAM1_DP2-Pad141)") (class "Default")
      (node (ref "J13") (pin "141") (pinfunction "CAM1_DP2_141") (pintype "passive+no_connect"))
    )
    (net (code "114") (name "unconnected-(J13B-CAM1_DP3-Pad135)") (class "Default")
      (node (ref "J13") (pin "135") (pinfunction "CAM1_DP3_135") (pintype "passive+no_connect"))
    )
    (net (code "115") (name "unconnected-(J13B-DSI0_CN-Pad105)") (class "Default")
      (node (ref "J13") (pin "105") (pinfunction "DSI0_CN_105") (pintype "passive+no_connect"))
    )
    (net (code "116") (name "unconnected-(J13B-DSI0_CP-Pad107)") (class "Default")
      (node (ref "J13") (pin "107") (pinfunction "DSI0_CP_107") (pintype "passive+no_connect"))
    )
    (net (code "117") (name "unconnected-(J13B-DSI0_DP0-Pad101)") (class "Default")
      (node (ref "J13") (pin "101") (pinfunction "DSI0_DP0_101") (pintype "passive+no_connect"))
    )
    (net (code "118") (name "unconnected-(J13B-DSI1_DN2-Pad114)") (class "Default")
      (node (ref "J13") (pin "114") (pinfunction "DSI1_DN2_114") (pintype "passive+no_connect"))
    )
    (net (code "119") (name "unconnected-(J13B-DSI1_DN3-Pad108)") (class "Default")
      (node (ref "J13") (pin "108") (pinfunction "DSI1_DN3_108") (pintype "passive+no_connect"))
    )
    (net (code "120") (name "unconnected-(J13B-DSI1_DP2-Pad112)") (class "Default")
      (node (ref "J13") (pin "112") (pinfunction "DSI1_DP2_112") (pintype "passive+no_connect"))
    )
    (net (code "121") (name "unconnected-(J13B-DSI1_DP3-Pad106)") (class "Default")
      (node (ref "J13") (pin "106") (pinfunction "DSI1_DP3_106") (pintype "passive+no_connect"))
    )
    (net (code "122") (name "unconnected-(J13B-NC-Pad124)") (class "Default")
      (node (ref "J13") (pin "124") (pinfunction "NC_124") (pintype "passive+no_connect"))
    )
    (net (code "123") (name "unconnected-(J13B-NC-Pad126)") (class "Default")
      (node (ref "J13") (pin "126") (pinfunction "NC_126") (pintype "passive+no_connect"))
    )
    (net (code "124") (name "unconnected-(J13B-NC-Pad128)") (class "Default")
      (node (ref "J13") (pin "128") (pinfunction "NC_128") (pintype "passive+no_connect"))
    )
    (net (code "125") (name "unconnected-(J13B-NC-Pad130)") (class "Default")
      (node (ref "J13") (pin "130") (pinfunction "NC_130") (pintype "passive+no_connect"))
    )
    (net (code "126") (name "unconnected-(J13B-NC-Pad132)") (class "Default")
      (node (ref "J13") (pin "132") (pinfunction "NC_132") (pintype "passive+no_connect"))
    )
    (net (code "127") (name "unconnected-(J13B-NC-Pad154)") (class "Default")
      (node (ref "J13") (pin "154") (pinfunction "NC_154") (pintype "passive+no_connect"))
    )
    (net (code "128") (name "unconnected-(J13B-NC-Pad156)") (class "Default")
      (node (ref "J13") (pin "156") (pinfunction "NC_156") (pintype "passive+no_connect"))
    )
    (net (code "129") (name "unconnected-(J13B-NC-Pad158)") (class "Default")
      (node (ref "J13") (pin "158") (pinfunction "NC_158") (pintype "passive+no_connect"))
    )
    (net (code "130") (name "unconnected-(J13B-NC-Pad160)") (class "Default")
      (node (ref "J13") (pin "160") (pinfunction "NC_160") (pintype "passive+no_connect"))
    )
    (net (code "131") (name "unconnected-(J13B-NC-Pad162)") (class "Default")
      (node (ref "J13") (pin "162") (pinfunction "NC_162") (pintype "passive+no_connect"))
    )
    (net (code "132") (name "unconnected-(J13B-VC_TCK-Pad180)") (class "Default")
      (node (ref "J13") (pin "180") (pinfunction "VC_TCK_180") (pintype "passive+no_connect"))
    )
    (net (code "133") (name "unconnected-(J13B-VC_TDI-Pad174)") (class "Default")
      (node (ref "J13") (pin "174") (pinfunction "VC_TDI_174") (pintype "passive+no_connect"))
    )
    (net (code "134") (name "unconnected-(J13B-VC_TDO-Pad178)") (class "Default")
      (node (ref "J13") (pin "178") (pinfunction "VC_TDO_178") (pintype "passive+no_connect"))
    )
    (net (code "135") (name "unconnected-(J13B-VC_TMS-Pad176)") (class "Default")
      (node (ref "J13") (pin "176") (pinfunction "VC_TMS_176") (pintype "passive+no_connect"))
    )
    (net (code "136") (name "unconnected-(J13B-VC_TRST_N-Pad172)") (class "Default")
      (node (ref "J13") (pin "172") (pinfunction "VC_TRST_N_172") (pintype "passive+no_connect"))
    )
    (net (code "137") (name "unconnected-(J13B-VDD_CORE_(DO_NOT_CONNECT)-Pad179)") (class "Default")
      (node (ref "J13") (pin "179") (pinfunction "VDD_CORE_(DO_NOT_CONNECT)_179") (pintype "passive+no_connect"))
    )
    (net (code "138") (name "unconnected-(JMP1-Pad1)") (class "Default")
      (node (ref "JMP1") (pin "1") (pinfunction "1_1") (pintype "passive"))
    )
    (net (code "139") (name "unconnected-(JMP1-Pad2)") (class "Default")
      (node (ref "JMP1") (pin "2") (pinfunction "2_2") (pintype "passive"))
    )
  )
)
